# EEM_connector.net
KiCad netlist of a schematic drawn in Altium Designer
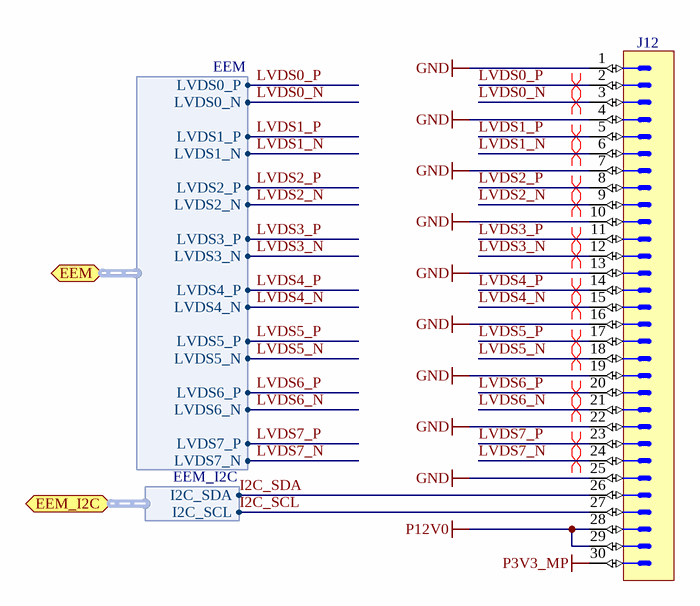
[diagram p0: EEM_connector.SchDoc]

(export (version "E")
  (design (tool "Eeschema 10.0.6"))
  (components
    (comp (ref "J12")
      (value "~")
      (footprint "3M_N2530-6002RB")
      (description "Connector 30 Male")
      (fields
        (field (name "PART NUMBER") "3M_N2530-6002RB")
        (field (name "MANUFACTURER") "3M")
        (field (name "AUTHOR") "CERN DEM JLC")
      )
      (libsource (lib "Connectors") (part "Connector 30 Male"))
    )
  )
  (nets
    (net (code "3") (name "/I2C_SCL") (class "Default")
      (node (ref "J12") (pin "27") (pinfunction "27_27") (pintype "bidirectional"))
    )
    (net (code "4") (name "/I2C_SDA") (class "Default")
      (node (ref "J12") (pin "26") (pinfunction "26_26") (pintype "bidirectional"))
    )
    (net (code "5") (name "/LVDS0_N") (class "Default")
      (node (ref "J12") (pin "3") (pinfunction "3_3") (pintype "bidirectional"))
    )
    (net (code "6") (name "/LVDS0_P") (class "Default")
      (node (ref "J12") (pin "2") (pinfunction "2_2") (pintype "bidirectional"))
    )
    (net (code "7") (name "/LVDS1_N") (class "Default")
      (node (ref "J12") (pin "6") (pinfunction "6_6") (pintype "bidirectional"))
    )
    (net (code "8") (name "/LVDS1_P") (class "Default")
      (node (ref "J12") (pin "5") (pinfunction "5_5") (pintype "bidirectional"))
    )
    (net (code "9") (name "/LVDS2_N") (class "Default")
      (node (ref "J12") (pin "9") (pinfunction "9_9") (pintype "bidirectional"))
    )
    (net (code "10") (name "/LVDS2_P") (class "Default")
      (node (ref "J12") (pin "8") (pinfunction "8_8") (pintype "bidirectional"))
    )
    (net (code "11") (name "/LVDS3_N") (class "Default")
      (node (ref "J12") (pin "12") (pinfunction "12_12") (pintype "bidirectional"))
    )
    (net (code "12") (name "/LVDS3_P") (class "Default")
      (node (ref "J12") (pin "11") (pinfunction "11_11") (pintype "bidirectional"))
    )
    (net (code "13") (name "/LVDS4_N") (class "Default")
      (node (ref "J12") (pin "15") (pinfunction "15_15") (pintype "bidirectional"))
    )
    (net (code "14") (name "/LVDS4_P") (class "Default")
      (node (ref "J12") (pin "14") (pinfunction "14_14") (pintype "bidirectional"))
    )
    (net (code "15") (name "/LVDS5_N") (class "Default")
      (node (ref "J12") (pin "18") (pinfunction "18_18") (pintype "bidirectional"))
    )
    (net (code "16") (name "/LVDS5_P") (class "Default")
      (node (ref "J12") (pin "17") (pinfunction "17_17") (pintype "bidirectional"))
    )
    (net (code "17") (name "/LVDS6_N") (class "Default")
      (node (ref "J12") (pin "21") (pinfunction "21_21") (pintype "bidirectional"))
    )
    (net (code "18") (name "/LVDS6_P") (class "Default")
      (node (ref "J12") (pin "20") (pinfunction "20_20") (pintype "bidirectional"))
    )
    (net (code "19") (name "/LVDS7_N") (class "Default")
      (node (ref "J12") (pin "24") (pinfunction "24_24") (pintype "bidirectional"))
    )
    (net (code "20") (name "/LVDS7_P") (class "Default")
      (node (ref "J12") (pin "23") (pinfunction "23_23") (pintype "bidirectional"))
    )
    (net (code "23") (name "GND") (class "Default")
      (node (ref "J12") (pin "1") (pinfunction "1_1") (pintype "bidirectional"))
      (node (ref "J12") (pin "10") (pinfunction "10_10") (pintype "bidirectional"))
      (node (ref "J12") (pin "13") (pinfunction "13_13") (pintype "bidirectional"))
      (node (ref "J12") (pin "16") (pinfunction "16_16") (pintype "bidirectional"))
      (node (ref "J12") (pin "19") (pinfunction "19_19") (pintype "bidirectional"))
      (node (ref "J12") (pin "22") (pinfunction "22_22") (pintype "bidirectional"))
      (node (ref "J12") (pin "25") (pinfunction "25_25") (pintype "bidirectional"))
      (node (ref "J12") (pin "4") (pinfunction "4_4") (pintype "bidirectional"))
      (node (ref "J12") (pin "7") (pinfunction "7_7") (pintype "bidirectional"))
    )
    (net (code "24") (name "P3V3_MP") (class "Default")
      (node (ref "J12") (pin "30") (pinfunction "30_30") (pintype "bidirectional"))
    )
    (net (code "25") (name "P12V0") (class "Default")
      (node (ref "J12") (pin "28") (pinfunction "28_28") (pintype "bidirectional"))
      (node (ref "J12") (pin "29") (pinfunction "29_29") (pintype "bidirectional"))
    )
  )
)
